# LeftBar1_SchDoc.net
KiCad netlist of a schematic drawn in Altium Designer
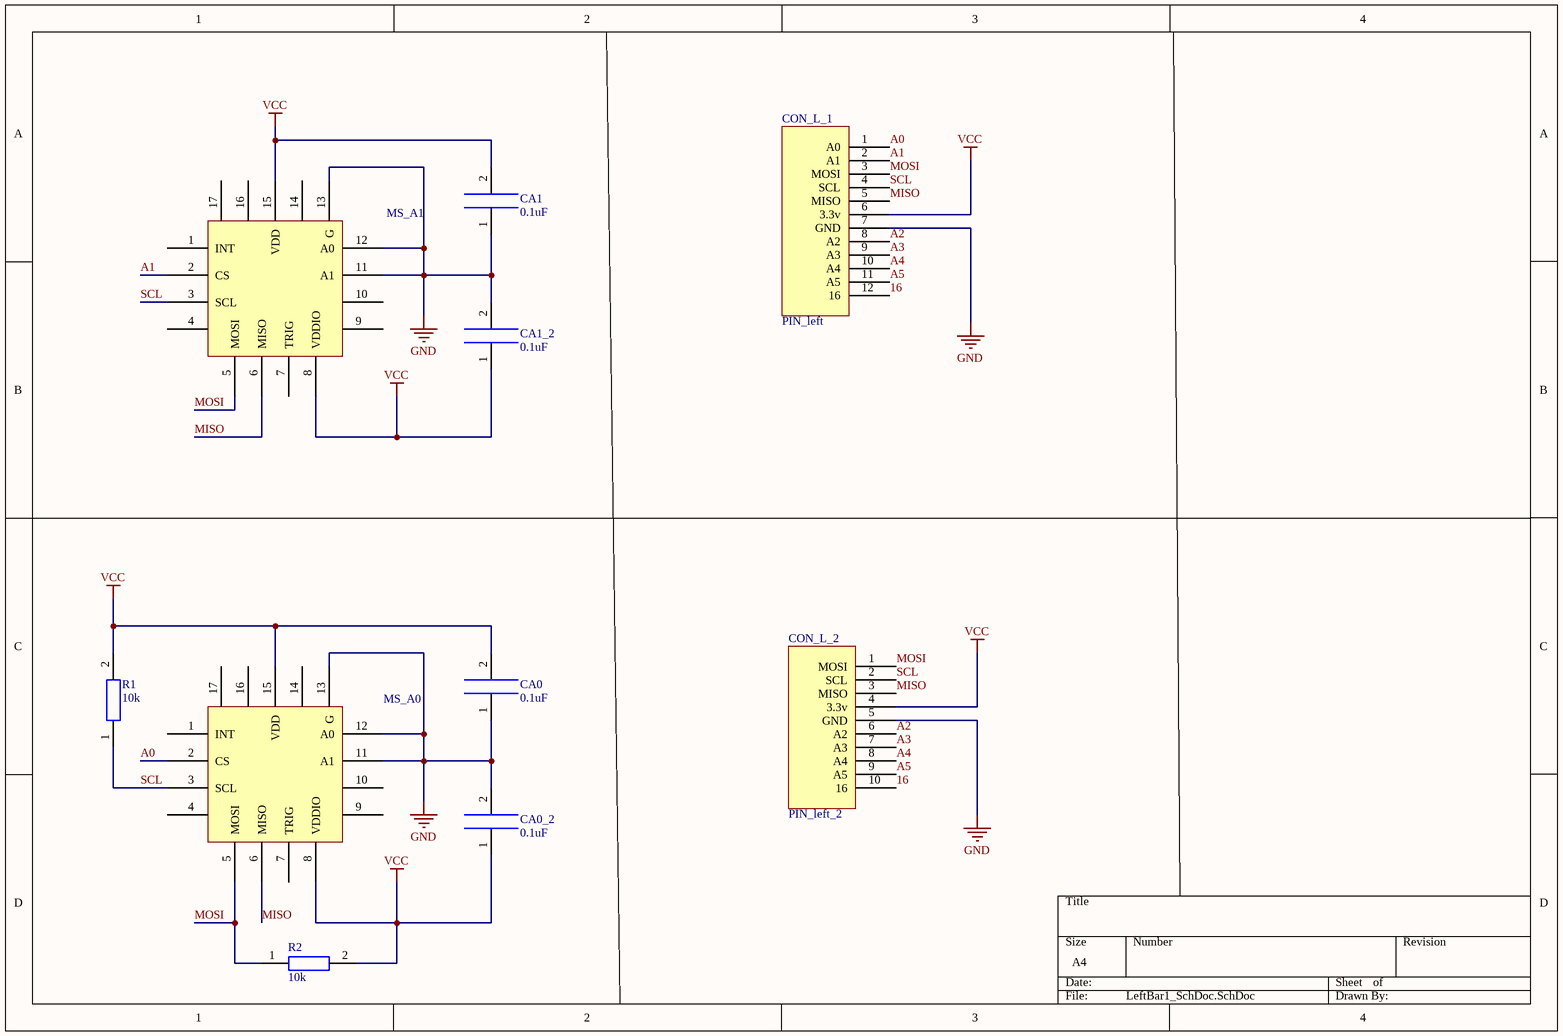
[diagram p0: LeftBar1_SchDoc.SchDoc]

(export (version "E")
  (design (tool "Eeschema 10.0.6"))
  (components
    (comp (ref "CA0")
      (value "0.1uF")
      (footprint "CAP_0603")
      (description "Capacitance")
      (libsource (lib "MagWaySchlib") (part "CAP"))
    )
    (comp (ref "CA0_2")
      (value "0.1uF")
      (footprint "CAP_0603")
      (description "Capacitance")
      (libsource (lib "MagWaySchlib") (part "CAP"))
    )
    (comp (ref "CA1")
      (value "0.1uF")
      (footprint "CAP_0603")
      (description "Capacitance")
      (libsource (lib "MagWaySchlib") (part "CAP"))
    )
    (comp (ref "CA1_2")
      (value "0.1uF")
      (footprint "CAP_0603")
      (description "Capacitance")
      (libsource (lib "MagWaySchlib") (part "CAP"))
    )
    (comp (ref "CON_L_1")
      (value "PIN_left")
      (footprint "PIN_left")
      (libsource (lib "MagWaySchlib") (part "PIN_left"))
    )
    (comp (ref "CON_L_2")
      (value "PIN_left_2")
      (footprint "PIN_Left_2")
      (libsource (lib "MagWaySchlib") (part "PIN_left_2"))
    )
    (comp (ref "MS_A0")
      (value "MLX90393SLW ABA 011 RE")
      (footprint "MLX90393")
      (description "MLX90393 Sensor")
      (libsource (lib "MagWaySchlib") (part "MLX90393SLW ABA 011 RE"))
    )
    (comp (ref "MS_A1")
      (value "MLX90393SLW ABA 011 RE")
      (footprint "MLX90393")
      (description "MLX90393 Sensor")
      (libsource (lib "MagWaySchlib") (part "MLX90393SLW ABA 011 RE"))
    )
    (comp (ref "R1")
      (value "10k")
      (footprint "RES_0603")
      (description "Resistance")
      (libsource (lib "MagWaySchlib") (part "RES"))
    )
    (comp (ref "R2")
      (value "10k")
      (footprint "RES_0603")
      (description "Resistance")
      (libsource (lib "MagWaySchlib") (part "RES"))
    )
  )
  (nets
    (net (code "1") (name "/16") (class "Default")
      (node (ref "CON_L_1") (pin "12") (pinfunction "16_12") (pintype "passive"))
      (node (ref "CON_L_2") (pin "10") (pinfunction "16_10") (pintype "passive"))
    )
    (net (code "2") (name "/A0") (class "Default")
      (node (ref "CON_L_1") (pin "1") (pinfunction "A0_1") (pintype "passive"))
      (node (ref "MS_A0") (pin "2") (pinfunction "CS_2") (pintype "passive"))
    )
    (net (code "3") (name "/A1") (class "Default")
      (node (ref "CON_L_1") (pin "2") (pinfunction "A1_2") (pintype "passive"))
      (node (ref "MS_A1") (pin "2") (pinfunction "CS_2") (pintype "passive"))
    )
    (net (code "4") (name "/A2") (class "Default")
      (node (ref "CON_L_1") (pin "8") (pinfunction "A2_8") (pintype "passive"))
      (node (ref "CON_L_2") (pin "6") (pinfunction "A2_6") (pintype "passive"))
    )
    (net (code "5") (name "/A3") (class "Default")
      (node (ref "CON_L_1") (pin "9") (pinfunction "A3_9") (pintype "passive"))
      (node (ref "CON_L_2") (pin "7") (pinfunction "A3_7") (pintype "passive"))
    )
    (net (code "6") (name "/A4") (class "Default")
      (node (ref "CON_L_1") (pin "10") (pinfunction "A4_10") (pintype "passive"))
      (node (ref "CON_L_2") (pin "8") (pinfunction "A4_8") (pintype "passive"))
    )
    (net (code "7") (name "/A5") (class "Default")
      (node (ref "CON_L_1") (pin "11") (pinfunction "A5_11") (pintype "passive"))
      (node (ref "CON_L_2") (pin "9") (pinfunction "A5_9") (pintype "passive"))
    )
    (net (code "8") (name "/MISO") (class "Default")
      (node (ref "CON_L_1") (pin "5") (pinfunction "MISO_5") (pintype "passive"))
      (node (ref "CON_L_2") (pin "3") (pinfunction "MISO_3") (pintype "passive"))
      (node (ref "MS_A0") (pin "6") (pinfunction "MISO_6") (pintype "passive"))
      (node (ref "MS_A1") (pin "6") (pinfunction "MISO_6") (pintype "passive"))
    )
    (net (code "9") (name "/MOSI") (class "Default")
      (node (ref "CON_L_1") (pin "3") (pinfunction "MOSI_3") (pintype "passive"))
      (node (ref "CON_L_2") (pin "1") (pinfunction "MOSI_1") (pintype "passive"))
      (node (ref "MS_A0") (pin "5") (pinfunction "MOSI_5") (pintype "passive"))
      (node (ref "MS_A1") (pin "5") (pinfunction "MOSI_5") (pintype "passive"))
      (node (ref "R2") (pin "1") (pintype "passive"))
    )
    (net (code "10") (name "/SCL") (class "Default")
      (node (ref "CON_L_1") (pin "4") (pinfunction "SCL_4") (pintype "passive"))
      (node (ref "CON_L_2") (pin "2") (pinfunction "SCL_2") (pintype "passive"))
      (node (ref "MS_A0") (pin "3") (pinfunction "SCL_3") (pintype "passive"))
      (node (ref "MS_A1") (pin "3") (pinfunction "SCL_3") (pintype "passive"))
      (node (ref "R1") (pin "1") (pintype "passive"))
    )
    (net (code "11") (name "GND") (class "Default")
      (node (ref "CA0") (pin "1") (pintype "passive"))
      (node (ref "CA0_2") (pin "2") (pintype "passive"))
      (node (ref "CA1") (pin "1") (pintype "passive"))
      (node (ref "CA1_2") (pin "2") (pintype "passive"))
      (node (ref "CON_L_1") (pin "7") (pinfunction "GND_7") (pintype "passive"))
      (node (ref "CON_L_2") (pin "5") (pinfunction "GND_5") (pintype "passive"))
      (node (ref "MS_A0") (pin "11") (pinfunction "A1_11") (pintype "passive"))
      (node (ref "MS_A0") (pin "12") (pinfunction "A0_12") (pintype "passive"))
      (node (ref "MS_A0") (pin "13") (pinfunction "G_13") (pintype "passive"))
      (node (ref "MS_A1") (pin "11") (pinfunction "A1_11") (pintype "passive"))
      (node (ref "MS_A1") (pin "12") (pinfunction "A0_12") (pintype "passive"))
      (node (ref "MS_A1") (pin "13") (pinfunction "G_13") (pintype "passive"))
    )
    (net (code "12") (name "VCC") (class "Default")
      (node (ref "CA0") (pin "2") (pintype "passive"))
      (node (ref "CA0_2") (pin "1") (pintype "passive"))
      (node (ref "CA1") (pin "2") (pintype "passive"))
      (node (ref "CA1_2") (pin "1") (pintype "passive"))
      (node (ref "CON_L_1") (pin "6") (pinfunction "3.3v_6") (pintype "passive"))
      (node (ref "CON_L_2") (pin "4") (pinfunction "3.3v_4") (pintype "passive"))
      (node (ref "MS_A0") (pin "15") (pinfunction "VDD_15") (pintype "passive"))
      (node (ref "MS_A0") (pin "8") (pinfunction "VDDIO_8") (pintype "passive"))
      (node (ref "MS_A1") (pin "15") (pinfunction "VDD_15") (pintype "passive"))
      (node (ref "MS_A1") (pin "8") (pinfunction "VDDIO_8") (pintype "passive"))
      (node (ref "R1") (pin "2") (pintype "passive"))
      (node (ref "R2") (pin "2") (pintype "passive"))
    )
    (net (code "13") (name "unconnected-(MS_A0-INT-Pad1)") (class "Default")
      (node (ref "MS_A0") (pin "1") (pinfunction "INT_1") (pintype "passive"))
    )
    (net (code "14") (name "unconnected-(MS_A0-Pad4)") (class "Default")
      (node (ref "MS_A0") (pin "4") (pintype "passive"))
    )
    (net (code "15") (name "unconnected-(MS_A0-Pad9)") (class "Default")
      (node (ref "MS_A0") (pin "9") (pintype "passive"))
    )
    (net (code "16") (name "unconnected-(MS_A0-Pad10)") (class "Default")
      (node (ref "MS_A0") (pin "10") (pintype "passive"))
    )
    (net (code "17") (name "unconnected-(MS_A0-Pad14)") (class "Default")
      (node (ref "MS_A0") (pin "14") (pintype "passive"))
    )
    (net (code "18") (name "unconnected-(MS_A0-Pad16)") (class "Default")
      (node (ref "MS_A0") (pin "16") (pintype "passive"))
    )
    (net (code "19") (name "unconnected-(MS_A0-Pad17)") (class "Default")
      (node (ref "MS_A0") (pin "17") (pintype "passive"))
    )
    (net (code "20") (name "unconnected-(MS_A0-TRIG-Pad7)") (class "Default")
      (node (ref "MS_A0") (pin "7") (pinfunction "TRIG_7") (pintype "passive"))
    )
    (net (code "21") (name "unconnected-(MS_A1-INT-Pad1)") (class "Default")
      (node (ref "MS_A1") (pin "1") (pinfunction "INT_1") (pintype "passive"))
    )
    (net (code "22") (name "unconnected-(MS_A1-Pad4)") (class "Default")
      (node (ref "MS_A1") (pin "4") (pintype "passive"))
    )
    (net (code "23") (name "unconnected-(MS_A1-Pad9)") (class "Default")
      (node (ref "MS_A1") (pin "9") (pintype "passive"))
    )
    (net (code "24") (name "unconnected-(MS_A1-Pad10)") (class "Default")
      (node (ref "MS_A1") (pin "10") (pintype "passive"))
    )
    (net (code "25") (name "unconnected-(MS_A1-Pad14)") (class "Default")
      (node (ref "MS_A1") (pin "14") (pintype "passive"))
    )
    (net (code "26") (name "unconnected-(MS_A1-Pad16)") (class "Default")
      (node (ref "MS_A1") (pin "16") (pintype "passive"))
    )
    (net (code "27") (name "unconnected-(MS_A1-Pad17)") (class "Default")
      (node (ref "MS_A1") (pin "17") (pintype "passive"))
    )
    (net (code "28") (name "unconnected-(MS_A1-TRIG-Pad7)") (class "Default")
      (node (ref "MS_A1") (pin "7") (pinfunction "TRIG_7") (pintype "passive"))
    )
  )
)
